# 7_can_rc_i2c_analog.net
KiCad netlist of a schematic drawn in Altium Designer
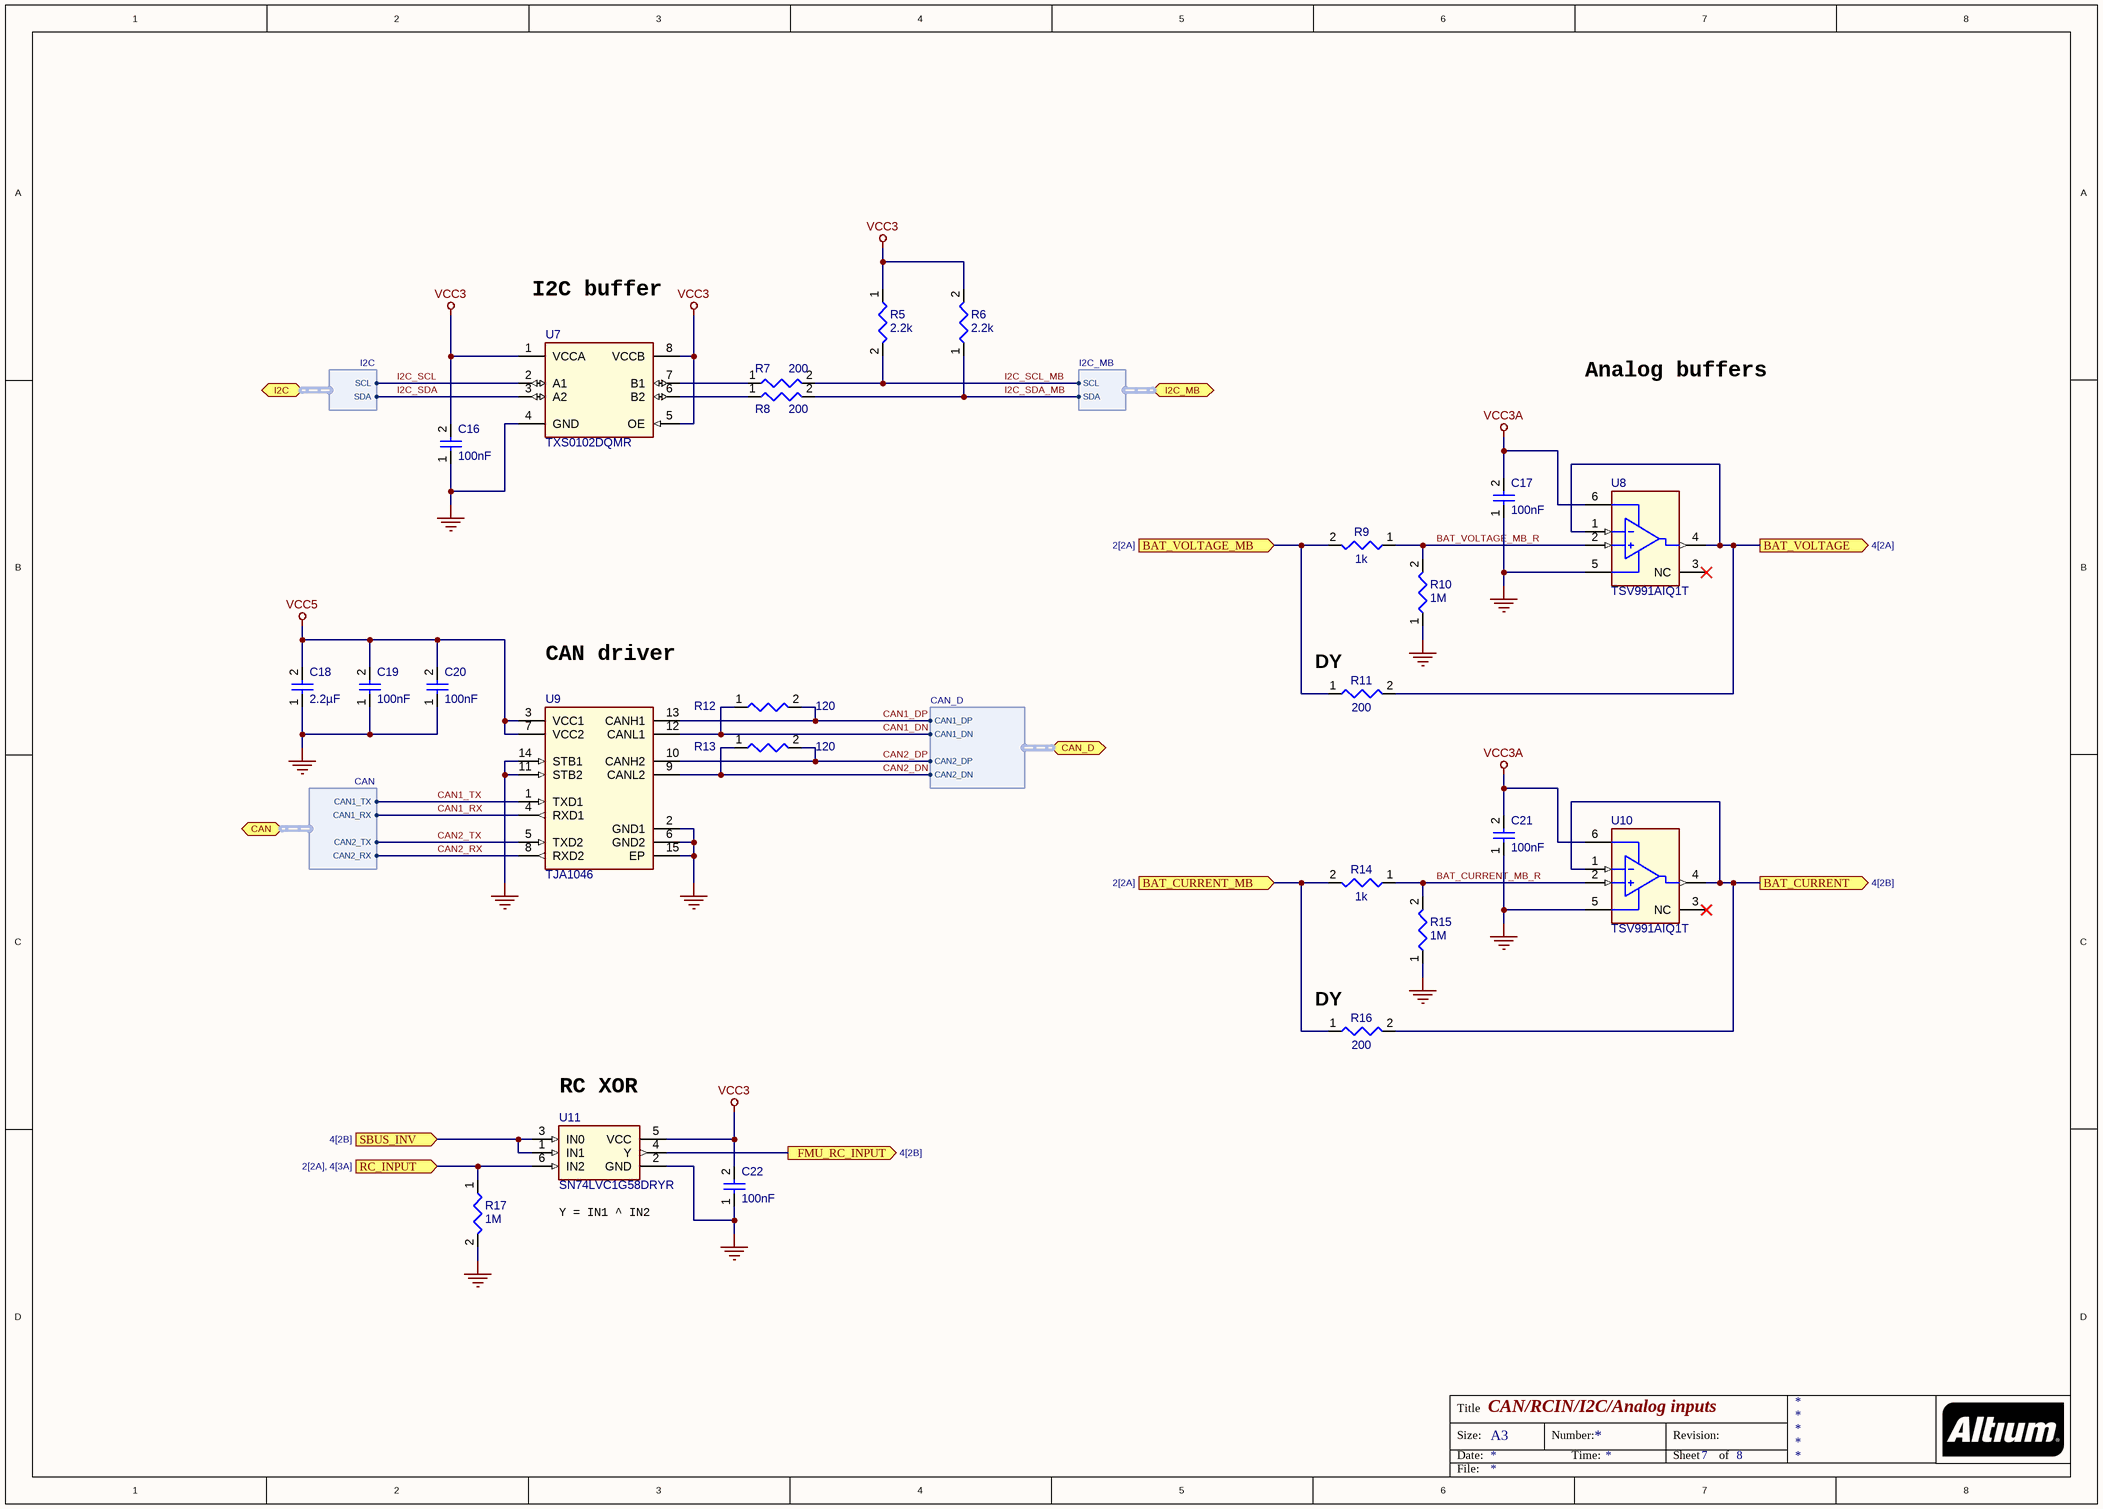
[diagram p0: 7_can_rc_i2c_analog.SchDoc]

(export (version "E")
  (design (tool "Eeschema 10.0.6"))
  (components
    (comp (ref "C16")
      (value "100nF")
      (footprint "CAPC0402(1005)60_L")
      (description "Chip Capacitor, 100nF +/-20%, 10V, 0402, Thickness 0.6 mm")
      (fields (field (name "TOLERANCE") "20%") (field (name "Comment") "Capacitor 100nF +/-20% 10V 0402"))
      (libsource (lib "<Company> Server") (part "CAP-NP-2"))
    )
    (comp (ref "C17")
      (value "100nF")
      (footprint "CAPC0402(1005)60_L")
      (description "Chip Capacitor, 100nF +/-20%, 10V, 0402, Thickness 0.6 mm")
      (fields (field (name "TOLERANCE") "20%") (field (name "Comment") "Capacitor 100nF +/-20% 10V 0402"))
      (libsource (lib "<Company> Server") (part "CAP-NP-2"))
    )
    (comp (ref "C18")
      (value "2.2µF")
      (footprint "CAPC0402(1005)60_L")
      (description "Chip Capacitor, 2,2µF +/-20%, 10V, 0402, Thickness 0.6 mm")
      (fields (field (name "TOLERANCE") "10%") (field (name "Comment") "Capacitor 2,2µF +/-20% 10V 0402"))
      (libsource (lib "<Company> Server") (part "CAP-NP-2"))
    )
    (comp (ref "C19")
      (value "100nF")
      (footprint "CAPC0402(1005)60_L")
      (description "Chip Capacitor, 100nF +/-20%, 10V, 0402, Thickness 0.6 mm")
      (fields (field (name "TOLERANCE") "20%") (field (name "Comment") "Capacitor 100nF +/-20% 10V 0402"))
      (libsource (lib "<Company> Server") (part "CAP-NP-2"))
    )
    (comp (ref "C20")
      (value "100nF")
      (footprint "CAPC0402(1005)60_L")
      (description "Chip Capacitor, 100nF +/-20%, 10V, 0402, Thickness 0.6 mm")
      (fields (field (name "TOLERANCE") "20%") (field (name "Comment") "Capacitor 100nF +/-20% 10V 0402"))
      (libsource (lib "<Company> Server") (part "CAP-NP-2"))
    )
    (comp (ref "C21")
      (value "100nF")
      (footprint "CAPC0402(1005)60_L")
      (description "Chip Capacitor, 100nF +/-20%, 10V, 0402, Thickness 0.6 mm")
      (fields (field (name "TOLERANCE") "20%") (field (name "Comment") "Capacitor 100nF +/-20% 10V 0402"))
      (libsource (lib "<Company> Server") (part "CAP-NP-2"))
    )
    (comp (ref "C22")
      (value "100nF")
      (footprint "CAPC0402(1005)60_L")
      (description "Chip Capacitor, 100nF +/-20%, 10V, 0402, Thickness 0.6 mm")
      (fields (field (name "TOLERANCE") "20%") (field (name "Comment") "Capacitor 100nF +/-20% 10V 0402"))
      (libsource (lib "<Company> Server") (part "CAP-NP-2"))
    )
    (comp (ref "R5")
      (value "2.2k")
      (footprint "RESC0402(1005)_L")
      (description "Chip Resistor, 2,2 kOhms, +/-5 %, 63 mW, -55 to 155 degC, 0402")
      (fields (field (name "POWER") "63mW") (field (name "TOLERANCE") "5%"))
      (libsource (lib "<Company> Server") (part "RES-2"))
    )
    (comp (ref "R6")
      (value "2.2k")
      (footprint "RESC0402(1005)_L")
      (description "Chip Resistor, 2,2 kOhms, +/-5 %, 63 mW, -55 to 155 degC, 0402")
      (fields (field (name "POWER") "63mW") (field (name "TOLERANCE") "5%"))
      (libsource (lib "<Company> Server") (part "RES-2"))
    )
    (comp (ref "R7")
      (value "200")
      (footprint "RESC0402(1005)_L")
      (description "Chip Resistor, 200 Ohms, +/-5 %, 63 mW, -55 to 155 degC, 0402")
      (fields (field (name "POWER") "63mW") (field (name "TOLERANCE") "5%"))
      (libsource (lib "<Company> Server") (part "RES-2"))
    )
    (comp (ref "R8")
      (value "200")
      (footprint "RESC0402(1005)_L")
      (description "Chip Resistor, 200 Ohms, +/-5 %, 63 mW, -55 to 155 degC, 0402")
      (fields (field (name "POWER") "63mW") (field (name "TOLERANCE") "5%"))
      (libsource (lib "<Company> Server") (part "RES-2"))
    )
    (comp (ref "R9")
      (value "1k")
      (footprint "RESC0402(1005)_L")
      (description "Chip Resistor, 1 kOhms, +/-5 %, 63 mW, -55 to 155 degC, 0402")
      (fields (field (name "TOLERANCE") "5%") (field (name "POWER") "63mW"))
      (libsource (lib "<Company> Server") (part "RES-2"))
    )
    (comp (ref "R10")
      (value "1M")
      (footprint "RESC0402(1005)_L")
      (description "Chip Resistor, 1 MOhms, +/-5 %, 63 mW, -55 to 155 degC, 0402")
      (fields (field (name "TOLERANCE") "5%") (field (name "POWER") "63mW"))
      (libsource (lib "<Company> Server") (part "RES-2"))
    )
    (comp (ref "R11")
      (value "200")
      (footprint "RESC0402(1005)_L")
      (description "Chip Resistor, 200 Ohms, +/-5 %, 63 mW, -55 to 155 degC, 0402")
      (fields (field (name "POWER") "63mW") (field (name "TOLERANCE") "5%"))
      (libsource (lib "<Company> Server") (part "RES-2"))
    )
    (comp (ref "R12")
      (value "120")
      (footprint "RESC0603(1608)_L")
      (description "Chip Resistor, 120 Ohms, +/-5 %, 0.1 W, -55 to 155 degC, 0603")
      (fields (field (name "TOLERANCE") "5%") (field (name "POWER") "100mW"))
      (libsource (lib "<Company> Server") (part "RES-2"))
    )
    (comp (ref "R13")
      (value "120")
      (footprint "RESC0603(1608)_L")
      (description "Chip Resistor, 120 Ohms, +/-5 %, 0.1 W, -55 to 155 degC, 0603")
      (fields (field (name "TOLERANCE") "5%") (field (name "POWER") "100mW"))
      (libsource (lib "<Company> Server") (part "RES-2"))
    )
    (comp (ref "R14")
      (value "1k")
      (footprint "RESC0402(1005)_L")
      (description "Chip Resistor, 1 kOhms, +/-5 %, 63 mW, -55 to 155 degC, 0402")
      (fields (field (name "TOLERANCE") "5%") (field (name "POWER") "63mW"))
      (libsource (lib "<Company> Server") (part "RES-2"))
    )
    (comp (ref "R15")
      (value "1M")
      (footprint "RESC0402(1005)_L")
      (description "Chip Resistor, 1 MOhms, +/-5 %, 63 mW, -55 to 155 degC, 0402")
      (fields (field (name "TOLERANCE") "5%") (field (name "POWER") "63mW"))
      (libsource (lib "<Company> Server") (part "RES-2"))
    )
    (comp (ref "R16")
      (value "200")
      (footprint "RESC0402(1005)_L")
      (description "Chip Resistor, 200 Ohms, +/-5 %, 63 mW, -55 to 155 degC, 0402")
      (fields (field (name "POWER") "63mW") (field (name "TOLERANCE") "5%"))
      (libsource (lib "<Company> Server") (part "RES-2"))
    )
    (comp (ref "R17")
      (value "1M")
      (footprint "RESC0402(1005)_L")
      (description "Chip Resistor, 1 MOhms, +/-5 %, 63 mW, -55 to 155 degC, 0402")
      (fields (field (name "TOLERANCE") "5%") (field (name "POWER") "63mW"))
      (libsource (lib "<Company> Server") (part "RES-2"))
    )
    (comp (ref "U7")
      (value "TXS0102DQMR")
      (footprint "DQM")
      (description "IC TRANSLATOR VOLTAGE 8-X2SON")
      (libsource (lib "<Company> Server") (part "CMP-001-0022-1"))
    )
    (comp (ref "U8")
      (value "TSV991AIQ1T")
      (footprint "STM-DFN-8_V")
      (libsource (lib "<Company> Server") (part "CMP-001-0008-5"))
    )
    (comp (ref "U9")
      (value "TJA1046")
      (footprint "NXP-SOT1086-2_L")
      (libsource (lib "<Company> Server") (part "CMP-00180-5"))
    )
    (comp (ref "U10")
      (value "TSV991AIQ1T")
      (footprint "STM-DFN-8_V")
      (libsource (lib "<Company> Server") (part "CMP-001-0008-5"))
    )
    (comp (ref "U11")
      (value "SN74LVC1G58DRYR")
      (footprint "DRY0006A_V")
      (description "CONFIGURABLE MULTIPLE-FUNCTION GATE, DRY0006A, LARGE T&R")
      (libsource (lib "<Company> Server") (part "CMP-00132-5"))
    )
  )
  (nets
    (net (code "5") (name "/BAT_CURRENT") (class "Default")
      (node (ref "R16") (pin "2") (pinfunction "2_2") (pintype "passive"))
      (node (ref "U10") (pin "1") (pinfunction "IN-_1") (pintype "input"))
      (node (ref "U10") (pin "4") (pinfunction "OUT_4") (pintype "output"))
    )
    (net (code "6") (name "/BAT_CURRENT_MB") (class "Default")
      (node (ref "R14") (pin "2") (pinfunction "2_2") (pintype "passive"))
      (node (ref "R16") (pin "1") (pinfunction "1_1") (pintype "passive"))
    )
    (net (code "7") (name "/BAT_CURRENT_MB_R") (class "Default")
      (node (ref "R14") (pin "1") (pinfunction "1_1") (pintype "passive"))
      (node (ref "R15") (pin "2") (pinfunction "2_2") (pintype "passive"))
      (node (ref "U10") (pin "2") (pinfunction "IN+_2") (pintype "input"))
    )
    (net (code "8") (name "/BAT_VOLTAGE") (class "Default")
      (node (ref "R11") (pin "2") (pinfunction "2_2") (pintype "passive"))
      (node (ref "U8") (pin "1") (pinfunction "IN-_1") (pintype "input"))
      (node (ref "U8") (pin "4") (pinfunction "OUT_4") (pintype "output"))
    )
    (net (code "9") (name "/BAT_VOLTAGE_MB") (class "Default")
      (node (ref "R11") (pin "1") (pinfunction "1_1") (pintype "passive"))
      (node (ref "R9") (pin "2") (pinfunction "2_2") (pintype "passive"))
    )
    (net (code "10") (name "/BAT_VOLTAGE_MB_R") (class "Default")
      (node (ref "R10") (pin "2") (pinfunction "2_2") (pintype "passive"))
      (node (ref "R9") (pin "1") (pinfunction "1_1") (pintype "passive"))
      (node (ref "U8") (pin "2") (pinfunction "IN+_2") (pintype "input"))
    )
    (net (code "11") (name "/CAN1_DN") (class "Default")
      (node (ref "R12") (pin "1") (pinfunction "1_1") (pintype "passive"))
      (node (ref "U9") (pin "12") (pinfunction "CANL1_12") (pintype "passive"))
    )
    (net (code "12") (name "/CAN1_DP") (class "Default")
      (node (ref "R12") (pin "2") (pinfunction "2_2") (pintype "passive"))
      (node (ref "U9") (pin "13") (pinfunction "CANH1_13") (pintype "passive"))
    )
    (net (code "13") (name "/CAN1_RX") (class "Default")
      (node (ref "U9") (pin "4") (pinfunction "RXD1_4") (pintype "output"))
    )
    (net (code "14") (name "/CAN1_TX") (class "Default")
      (node (ref "U9") (pin "1") (pinfunction "TXD1_1") (pintype "input"))
    )
    (net (code "15") (name "/CAN2_DN") (class "Default")
      (node (ref "R13") (pin "1") (pinfunction "1_1") (pintype "passive"))
      (node (ref "U9") (pin "9") (pinfunction "CANL2_9") (pintype "passive"))
    )
    (net (code "16") (name "/CAN2_DP") (class "Default")
      (node (ref "R13") (pin "2") (pinfunction "2_2") (pintype "passive"))
      (node (ref "U9") (pin "10") (pinfunction "CANH2_10") (pintype "passive"))
    )
    (net (code "17") (name "/CAN2_RX") (class "Default")
      (node (ref "U9") (pin "8") (pinfunction "RXD2_8") (pintype "output"))
    )
    (net (code "18") (name "/CAN2_TX") (class "Default")
      (node (ref "U9") (pin "5") (pinfunction "TXD2_5") (pintype "input"))
    )
    (net (code "19") (name "/FMU_RC_INPUT") (class "Default")
      (node (ref "U11") (pin "4") (pinfunction "Y_4") (pintype "output"))
    )
    (net (code "20") (name "/I2C_SCL") (class "Default")
      (node (ref "U7") (pin "2") (pinfunction "A1_2") (pintype "bidirectional"))
    )
    (net (code "21") (name "/I2C_SCL_MB") (class "Default")
      (node (ref "R5") (pin "2") (pinfunction "2_2") (pintype "passive"))
      (node (ref "R7") (pin "2") (pinfunction "2_2") (pintype "passive"))
    )
    (net (code "22") (name "/I2C_SDA") (class "Default")
      (node (ref "U7") (pin "3") (pinfunction "A2_3") (pintype "bidirectional"))
    )
    (net (code "23") (name "/I2C_SDA_MB") (class "Default")
      (node (ref "R6") (pin "1") (pinfunction "1_1") (pintype "passive"))
      (node (ref "R8") (pin "2") (pinfunction "2_2") (pintype "passive"))
    )
    (net (code "24") (name "/RC_INPUT") (class "Default")
      (node (ref "R17") (pin "1") (pinfunction "1_1") (pintype "passive"))
      (node (ref "U11") (pin "6") (pinfunction "IN2_6") (pintype "input"))
    )
    (net (code "25") (name "/SBUS_INV") (class "Default")
      (node (ref "U11") (pin "1") (pinfunction "IN1_1") (pintype "input"))
      (node (ref "U11") (pin "3") (pinfunction "IN0_3") (pintype "input"))
    )
    (net (code "30") (name "GND") (class "Default")
      (node (ref "C16") (pin "1") (pinfunction "1_1") (pintype "passive"))
      (node (ref "C17") (pin "1") (pinfunction "1_1") (pintype "passive"))
      (node (ref "C18") (pin "1") (pinfunction "1_1") (pintype "passive"))
      (node (ref "C19") (pin "1") (pinfunction "1_1") (pintype "passive"))
      (node (ref "C20") (pin "1") (pinfunction "1_1") (pintype "passive"))
      (node (ref "C21") (pin "1") (pinfunction "1_1") (pintype "passive"))
      (node (ref "C22") (pin "1") (pinfunction "1_1") (pintype "passive"))
      (node (ref "R10") (pin "1") (pinfunction "1_1") (pintype "passive"))
      (node (ref "R15") (pin "1") (pinfunction "1_1") (pintype "passive"))
      (node (ref "R17") (pin "2") (pinfunction "2_2") (pintype "passive"))
      (node (ref "U10") (pin "5") (pinfunction "VCC-_5") (pintype "power_in"))
      (node (ref "U11") (pin "2") (pinfunction "GND_2") (pintype "power_in"))
      (node (ref "U7") (pin "4") (pinfunction "GND_4") (pintype "power_in"))
      (node (ref "U8") (pin "5") (pinfunction "VCC-_5") (pintype "power_in"))
      (node (ref "U9") (pin "11") (pinfunction "STB2_11") (pintype "input"))
      (node (ref "U9") (pin "14") (pinfunction "STB1_14") (pintype "input"))
      (node (ref "U9") (pin "15") (pinfunction "EP_15") (pintype "power_in"))
      (node (ref "U9") (pin "2") (pinfunction "GND1_2") (pintype "power_in"))
      (node (ref "U9") (pin "6") (pinfunction "GND2_6") (pintype "power_in"))
    )
    (net (code "31") (name "Net-(U7-B1)") (class "Default")
      (node (ref "R7") (pin "1") (pinfunction "1_1") (pintype "passive"))
      (node (ref "U7") (pin "7") (pinfunction "B1_7") (pintype "bidirectional"))
    )
    (net (code "32") (name "Net-(U7-B2)") (class "Default")
      (node (ref "R8") (pin "1") (pinfunction "1_1") (pintype "passive"))
      (node (ref "U7") (pin "6") (pinfunction "B2_6") (pintype "bidirectional"))
    )
    (net (code "33") (name "VCC3") (class "Default")
      (node (ref "C16") (pin "2") (pinfunction "2_2") (pintype "passive"))
      (node (ref "C22") (pin "2") (pinfunction "2_2") (pintype "passive"))
      (node (ref "R5") (pin "1") (pinfunction "1_1") (pintype "passive"))
      (node (ref "R6") (pin "2") (pinfunction "2_2") (pintype "passive"))
      (node (ref "U11") (pin "5") (pinfunction "VCC_5") (pintype "power_in"))
      (node (ref "U7") (pin "1") (pinfunction "VCCA_1") (pintype "power_in"))
      (node (ref "U7") (pin "5") (pinfunction "OE_5") (pintype "input"))
      (node (ref "U7") (pin "8") (pinfunction "VCCB_8") (pintype "power_in"))
    )
    (net (code "34") (name "VCC3A") (class "Default")
      (node (ref "C17") (pin "2") (pinfunction "2_2") (pintype "passive"))
      (node (ref "C21") (pin "2") (pinfunction "2_2") (pintype "passive"))
      (node (ref "U10") (pin "6") (pinfunction "VCC+_6") (pintype "power_in"))
      (node (ref "U8") (pin "6") (pinfunction "VCC+_6") (pintype "power_in"))
    )
    (net (code "35") (name "VCC5") (class "Default")
      (node (ref "C18") (pin "2") (pinfunction "2_2") (pintype "passive"))
      (node (ref "C19") (pin "2") (pinfunction "2_2") (pintype "passive"))
      (node (ref "C20") (pin "2") (pinfunction "2_2") (pintype "passive"))
      (node (ref "U9") (pin "3") (pinfunction "VCC1_3") (pintype "power_in"))
      (node (ref "U9") (pin "7") (pinfunction "VCC2_7") (pintype "power_in"))
    )
    (net (code "36") (name "unconnected-(U8-NC-Pad3)") (class "Default")
      (node (ref "U8") (pin "3") (pinfunction "NC_3") (pintype "passive+no_connect"))
    )
    (net (code "37") (name "unconnected-(U10-NC-Pad3)") (class "Default")
      (node (ref "U10") (pin "3") (pinfunction "NC_3") (pintype "passive+no_connect"))
    )
  )
)
